# SCH_Blinky-Board_2025-12-09.net
KiCad netlist of a schematic drawn in EasyEDA
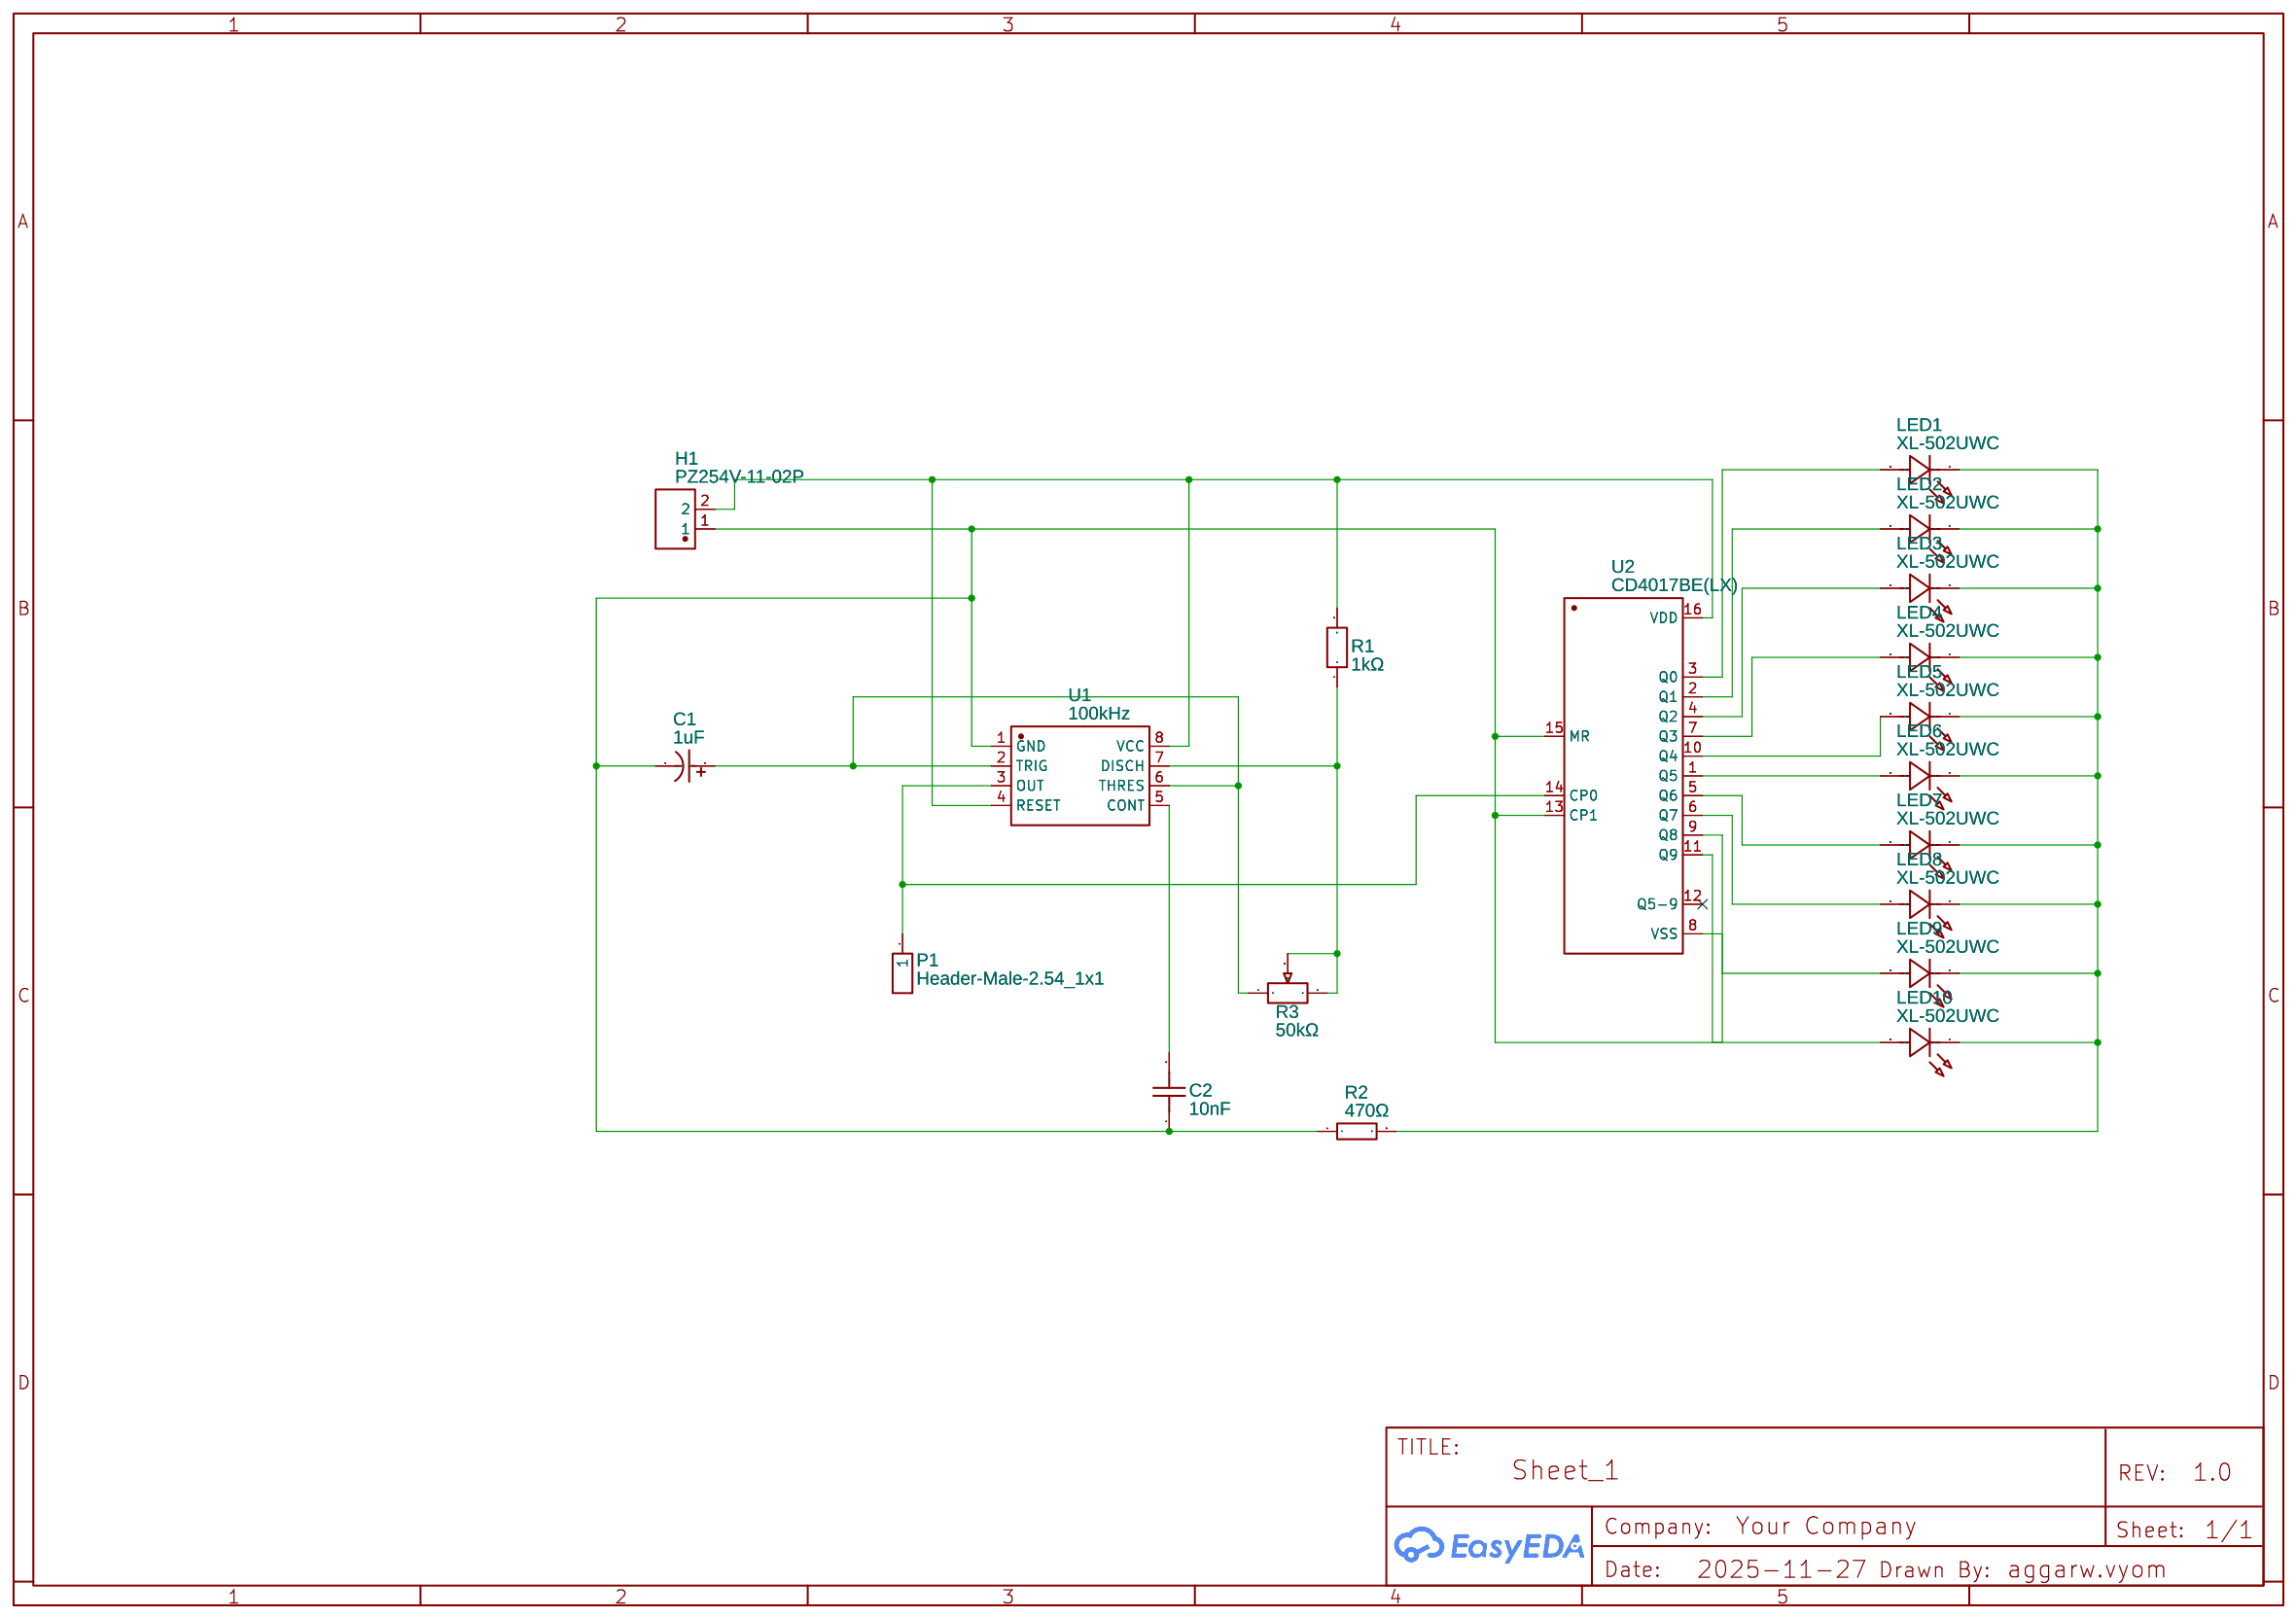
[diagram p0: schematic sheet]

(export (version "E")
  (design (tool "Eeschema 10.0.6"))
  (components
    (comp (ref "C1")
      (value "1uF")
      (fields (field (name "Manufacturer Part") "KF010M050C110A") (field (name "Manufacturer") "CapXon(丰宾)"))
      (libsource (lib "") (part "KF010M050C110A"))
    )
    (comp (ref "C2")
      (value "10nF")
      (fields (field (name "Manufacturer Part") "N09F1B103MN0B0S0N0") (field (name "Manufacturer") "STE(松田)"))
      (libsource (lib "") (part "N09F1B103MN0B0S0N0"))
    )
    (comp (ref "H1")
      (value "PZ254V-11-02P")
      (fields (field (name "Manufacturer") "XFCN(兴飞)"))
      (libsource (lib "") (part "PZ254V-11-02P"))
    )
    (comp (ref "LED1")
      (value "XL-502UWC")
      (fields (field (name "Manufacturer") "XINGLIGHT(成兴光)"))
      (libsource (lib "") (part "XL-502UWC"))
    )
    (comp (ref "LED2")
      (value "XL-502UWC")
      (fields (field (name "Manufacturer") "XINGLIGHT(成兴光)"))
      (libsource (lib "") (part "XL-502UWC"))
    )
    (comp (ref "LED3")
      (value "XL-502UWC")
      (fields (field (name "Manufacturer") "XINGLIGHT(成兴光)"))
      (libsource (lib "") (part "XL-502UWC"))
    )
    (comp (ref "LED4")
      (value "XL-502UWC")
      (fields (field (name "Manufacturer") "XINGLIGHT(成兴光)"))
      (libsource (lib "") (part "XL-502UWC"))
    )
    (comp (ref "LED5")
      (value "XL-502UWC")
      (fields (field (name "Manufacturer") "XINGLIGHT(成兴光)"))
      (libsource (lib "") (part "XL-502UWC"))
    )
    (comp (ref "LED6")
      (value "XL-502UWC")
      (fields (field (name "Manufacturer") "XINGLIGHT(成兴光)"))
      (libsource (lib "") (part "XL-502UWC"))
    )
    (comp (ref "LED7")
      (value "XL-502UWC")
      (fields (field (name "Manufacturer") "XINGLIGHT(成兴光)"))
      (libsource (lib "") (part "XL-502UWC"))
    )
    (comp (ref "LED8")
      (value "XL-502UWC")
      (fields (field (name "Manufacturer") "XINGLIGHT(成兴光)"))
      (libsource (lib "") (part "XL-502UWC"))
    )
    (comp (ref "LED9")
      (value "XL-502UWC")
      (fields (field (name "Manufacturer") "XINGLIGHT(成兴光)"))
      (libsource (lib "") (part "XL-502UWC"))
    )
    (comp (ref "LED10")
      (value "XL-502UWC")
      (fields (field (name "Manufacturer") "XINGLIGHT(成兴光)"))
      (libsource (lib "") (part "XL-502UWC"))
    )
    (comp (ref "P1")
      (value "Header-Male-2.54_1x1")
      (fields (field (name "Manufacturer Part") "2.54-1*1P针") (field (name "Manufacturer") "BOOMELE(博穆精密)"))
      (libsource (lib "") (part "Header-Male-2.54_1x1"))
    )
    (comp (ref "R1")
      (value "1kΩ")
      (fields (field (name "Manufacturer Part") "MF1/4W-1KΩ±1%T52") (field (name "Manufacturer") "华星机电"))
      (libsource (lib "") (part "MF1/4W-1KΩ±1%T52"))
    )
    (comp (ref "R2")
      (value "470Ω")
      (fields
        (field (name "Manufacturer Part") "MFR0W4F4700A50")
        (field (name "Manufacturer") "UNI-ROYAL(厚声)")
      )
      (libsource (lib "") (part "MFR0W4F4700A50"))
    )
    (comp (ref "R3")
      (value "50kΩ")
      (fields (field (name "Manufacturer Part") "3296X-1-503") (field (name "Manufacturer") "BOCHEN(博晨)"))
      (libsource (lib "") (part "3296X-1-503_C118912"))
    )
    (comp (ref "U1")
      (value "100kHz")
      (fields (field (name "Manufacturer Part") "NE555P") (field (name "Manufacturer") "TI(德州仪器)"))
      (libsource (lib "") (part "NE555P"))
    )
    (comp (ref "U2")
      (value "CD4017BE(LX)")
      (fields (field (name "Manufacturer") "LX(灵星芯微)"))
      (libsource (lib "") (part "CD4017BE(LX)"))
    )
  )
  (nets
    (net (code "1") (name "Net-(LED1-A)") (class "Default")
      (node (ref "LED1") (pin "2") (pinfunction "A_2") (pintype "unspecified"))
      (node (ref "U2") (pin "3") (pinfunction "Q0_3") (pintype "unspecified"))
    )
    (net (code "2") (name "Net-(LED1-K)") (class "Default")
      (node (ref "LED1") (pin "1") (pinfunction "K_1") (pintype "unspecified"))
      (node (ref "LED10") (pin "1") (pinfunction "K_1") (pintype "unspecified"))
      (node (ref "LED2") (pin "1") (pinfunction "K_1") (pintype "unspecified"))
      (node (ref "LED3") (pin "1") (pinfunction "K_1") (pintype "unspecified"))
      (node (ref "LED4") (pin "1") (pinfunction "K_1") (pintype "unspecified"))
      (node (ref "LED5") (pin "1") (pinfunction "K_1") (pintype "unspecified"))
      (node (ref "LED6") (pin "1") (pinfunction "K_1") (pintype "unspecified"))
      (node (ref "LED7") (pin "1") (pinfunction "K_1") (pintype "unspecified"))
      (node (ref "LED8") (pin "1") (pinfunction "K_1") (pintype "unspecified"))
      (node (ref "LED9") (pin "1") (pinfunction "K_1") (pintype "unspecified"))
      (node (ref "R2") (pin "2") (pinfunction "2_2") (pintype "input"))
    )
    (net (code "3") (name "Net-(LED2-A)") (class "Default")
      (node (ref "LED2") (pin "2") (pinfunction "A_2") (pintype "unspecified"))
      (node (ref "U2") (pin "2") (pinfunction "Q1_2") (pintype "unspecified"))
    )
    (net (code "4") (name "Net-(LED3-A)") (class "Default")
      (node (ref "LED3") (pin "2") (pinfunction "A_2") (pintype "unspecified"))
      (node (ref "U2") (pin "4") (pinfunction "Q2_4") (pintype "unspecified"))
    )
    (net (code "5") (name "Net-(LED4-A)") (class "Default")
      (node (ref "LED4") (pin "2") (pinfunction "A_2") (pintype "unspecified"))
      (node (ref "U2") (pin "7") (pinfunction "Q3_7") (pintype "unspecified"))
    )
    (net (code "6") (name "Net-(LED5-A)") (class "Default")
      (node (ref "LED5") (pin "2") (pinfunction "A_2") (pintype "unspecified"))
      (node (ref "U2") (pin "10") (pinfunction "Q4_10") (pintype "unspecified"))
    )
    (net (code "7") (name "Net-(LED6-A)") (class "Default")
      (node (ref "LED6") (pin "2") (pinfunction "A_2") (pintype "unspecified"))
      (node (ref "U2") (pin "1") (pinfunction "Q5_1") (pintype "unspecified"))
    )
    (net (code "8") (name "Net-(LED7-A)") (class "Default")
      (node (ref "LED7") (pin "2") (pinfunction "A_2") (pintype "unspecified"))
      (node (ref "U2") (pin "5") (pinfunction "Q6_5") (pintype "unspecified"))
    )
    (net (code "9") (name "Net-(LED8-A)") (class "Default")
      (node (ref "LED8") (pin "2") (pinfunction "A_2") (pintype "unspecified"))
      (node (ref "U2") (pin "6") (pinfunction "Q7_6") (pintype "unspecified"))
    )
    (net (code "10") (name "Net-(LED9-A)") (class "Default")
      (node (ref "LED9") (pin "2") (pinfunction "A_2") (pintype "unspecified"))
      (node (ref "U2") (pin "9") (pinfunction "Q8_9") (pintype "unspecified"))
    )
    (net (code "11") (name "Net-(LED10-A)") (class "Default")
      (node (ref "LED10") (pin "2") (pinfunction "A_2") (pintype "unspecified"))
      (node (ref "U2") (pin "11") (pinfunction "Q9_11") (pintype "unspecified"))
    )
    (net (code "12") (name "Net-(U1-CONT)") (class "Default")
      (node (ref "C2") (pin "2") (pinfunction "2_2") (pintype "unspecified"))
      (node (ref "U1") (pin "5") (pinfunction "CONT_5") (pintype "unspecified"))
    )
    (net (code "13") (name "Net-(U1-DISCH)") (class "Default")
      (node (ref "R1") (pin "1") (pinfunction "1_1") (pintype "unspecified"))
      (node (ref "R3") (pin "2") (pinfunction "2_2") (pintype "input"))
      (node (ref "R3") (pin "3") (pinfunction "3_3") (pintype "input"))
      (node (ref "U1") (pin "7") (pinfunction "DISCH_7") (pintype "unspecified"))
    )
    (net (code "14") (name "Net-(U1-GND)") (class "Default")
      (node (ref "C1") (pin "2") (pinfunction "2_2") (pintype "input"))
      (node (ref "C2") (pin "1") (pinfunction "1_1") (pintype "unspecified"))
      (node (ref "H1") (pin "1") (pinfunction "1_1") (pintype "unspecified"))
      (node (ref "R2") (pin "1") (pinfunction "1_1") (pintype "input"))
      (node (ref "U1") (pin "1") (pinfunction "GND_1") (pintype "unspecified"))
      (node (ref "U2") (pin "13") (pinfunction "CP1_13") (pintype "unspecified"))
      (node (ref "U2") (pin "15") (pinfunction "MR_15") (pintype "unspecified"))
      (node (ref "U2") (pin "8") (pinfunction "VSS_8") (pintype "unspecified"))
    )
    (net (code "15") (name "Net-(U1-OUT)") (class "Default")
      (node (ref "P1") (pin "1") (pinfunction "1_1") (pintype "input"))
      (node (ref "U1") (pin "3") (pinfunction "OUT_3") (pintype "unspecified"))
      (node (ref "U2") (pin "14") (pinfunction "CP0_14") (pintype "unspecified"))
    )
    (net (code "16") (name "Net-(U1-RESET)") (class "Default")
      (node (ref "H1") (pin "2") (pinfunction "2_2") (pintype "unspecified"))
      (node (ref "R1") (pin "2") (pinfunction "2_2") (pintype "unspecified"))
      (node (ref "U1") (pin "4") (pinfunction "RESET_4") (pintype "unspecified"))
      (node (ref "U1") (pin "8") (pinfunction "VCC_8") (pintype "unspecified"))
      (node (ref "U2") (pin "16") (pinfunction "VDD_16") (pintype "unspecified"))
    )
    (net (code "17") (name "Net-(U1-THRES)") (class "Default")
      (node (ref "C1") (pin "1") (pinfunction "1_1") (pintype "input"))
      (node (ref "R3") (pin "1") (pinfunction "1_1") (pintype "input"))
      (node (ref "U1") (pin "2") (pinfunction "TRIG_2") (pintype "unspecified"))
      (node (ref "U1") (pin "6") (pinfunction "THRES_6") (pintype "unspecified"))
    )
    (net (code "18") (name "unconnected-(U2-Q5-9-Pad12)") (class "Default")
      (node (ref "U2") (pin "12") (pinfunction "Q5-9_12") (pintype "unspecified+no_connect"))
    )
  )
)
